# 12_CAN_ADC_DAC.net
KiCad netlist of a schematic drawn in Altium Designer
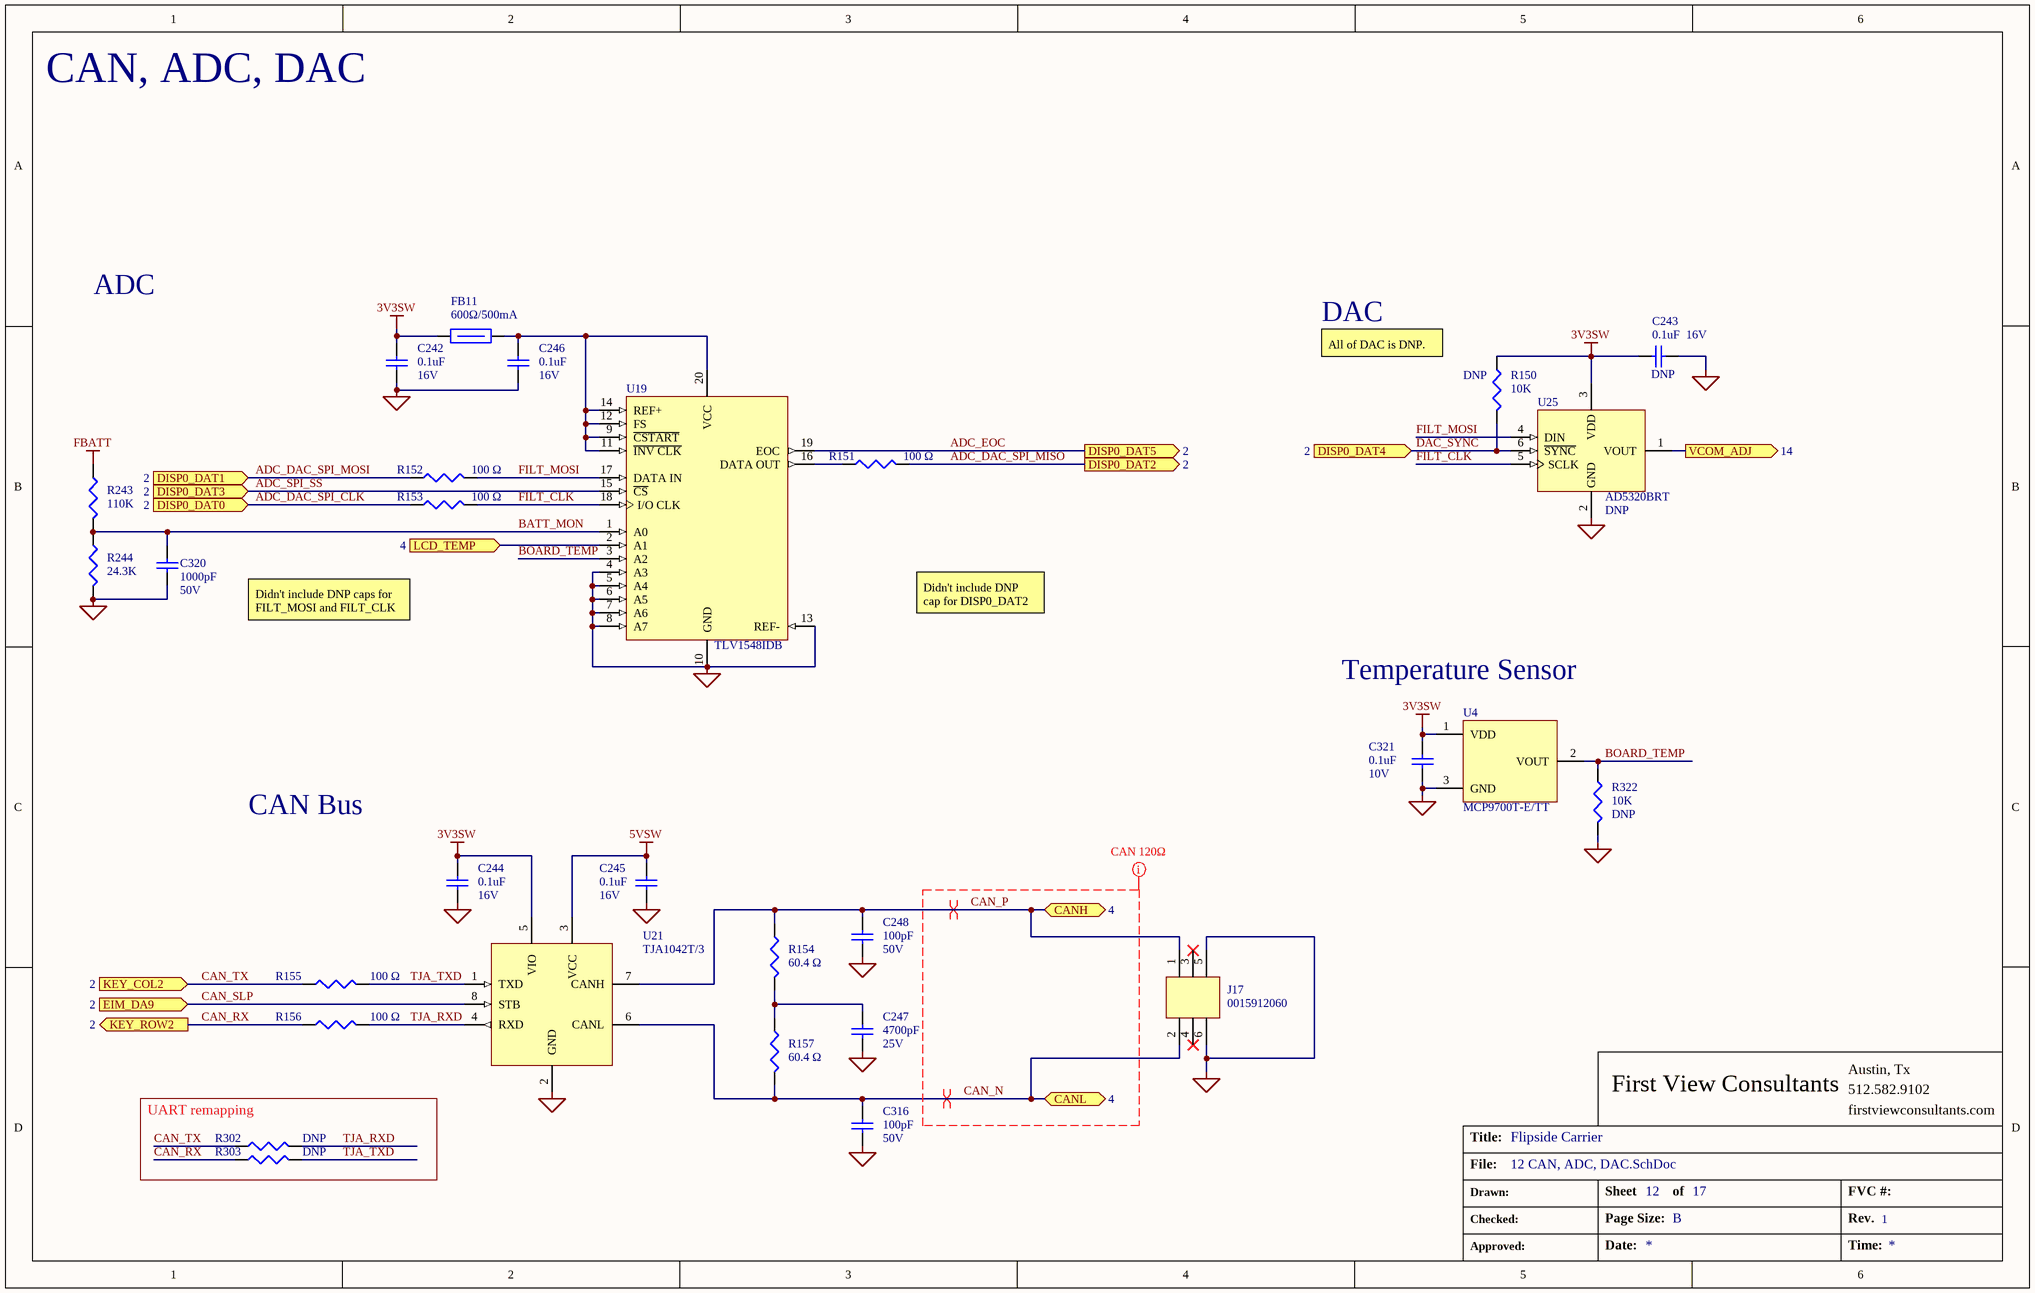
[diagram p0: 12 CAN, ADC, DAC.SchDoc]

(export (version "E")
  (design (tool "Eeschema 10.0.6"))
  (components
    (comp (ref "C242")
      (value "0.1uF")
      (footprint "CAP_0402")
      (description "Cap, Cer, 0.1uF, 16V, 10%, X7R, 0402")
      (fields
        (field (name "TOLERANCE") "±10%")
        (field (name "MANUFACTURER") "Murata Electronics North America")
        (field (name "VOLTAGE") "16V")
      )
      (libsource (lib "Firstview") (part "Cap 0.1uF 16V 0402"))
    )
    (comp (ref "C243")
      (value "0.1uF")
      (footprint "CAP_0402")
      (description "Cap, Cer, 0.1uF, 16V, 10%, X7R, 0402")
      (fields
        (field (name "TOLERANCE") "±10%")
        (field (name "DNP") "DNP")
        (field (name "MANUFACTURER") "Murata Electronics North America")
        (field (name "VOLTAGE") "16V")
      )
      (libsource (lib "Firstview") (part "Cap 0.1uF 16V 0402"))
    )
    (comp (ref "C244")
      (value "0.1uF")
      (footprint "CAP_0402")
      (description "Cap, Cer, 0.1uF, 16V, 10%, X7R, 0402")
      (fields
        (field (name "TOLERANCE") "±10%")
        (field (name "MANUFACTURER") "Murata Electronics North America")
        (field (name "VOLTAGE") "16V")
      )
      (libsource (lib "Firstview") (part "Cap 0.1uF 16V 0402"))
    )
    (comp (ref "C245")
      (value "0.1uF")
      (footprint "CAP_0402")
      (description "Cap, Cer, 0.1uF, 16V, 10%, X7R, 0402")
      (fields
        (field (name "TOLERANCE") "±10%")
        (field (name "MANUFACTURER") "Murata Electronics North America")
        (field (name "VOLTAGE") "16V")
      )
      (libsource (lib "Firstview") (part "Cap 0.1uF 16V 0402"))
    )
    (comp (ref "C246")
      (value "0.1uF")
      (footprint "CAP_0402")
      (description "Cap, Cer, 0.1uF, 16V, 10%, X7R, 0402")
      (fields
        (field (name "TOLERANCE") "±10%")
        (field (name "MANUFACTURER") "Murata Electronics North America")
        (field (name "VOLTAGE") "16V")
      )
      (libsource (lib "Firstview") (part "Cap 0.1uF 16V 0402"))
    )
    (comp (ref "C247")
      (value "4700pF")
      (footprint "CAP_0603")
      (description "Cap, Cer, 4700pF, 25V, 5%, C0G, 0603")
      (fields
        (field (name "TOLERANCE") "5%")
        (field (name "MANUFACTURER") "TDK Corporation")
        (field (name "VOLTAGE") "25V")
      )
      (libsource (lib "Firstview") (part "Cap 4700pF 25V 0603"))
    )
    (comp (ref "C248")
      (value "100pF")
      (footprint "CAP_0402")
      (description "Cap, Cer, 100pF, 50V, 5%, C0G/NP0, 0402")
      (fields
        (field (name "TOLERANCE") "5%")
        (field (name "MANUFACTURER") "Yageo")
        (field (name "VOLTAGE") "50V")
      )
      (libsource (lib "Firstview") (part "Cap 100pF 50V 0402"))
    )
    (comp (ref "C316")
      (value "100pF")
      (footprint "CAP_0402")
      (description "Cap, Cer, 100pF, 50V, 5%, C0G/NP0, 0402")
      (fields
        (field (name "TOLERANCE") "5%")
        (field (name "MANUFACTURER") "Yageo")
        (field (name "VOLTAGE") "50V")
      )
      (libsource (lib "Firstview") (part "Cap 100pF 50V 0402"))
    )
    (comp (ref "C320")
      (value "1000pF")
      (footprint "CAP_0402")
      (description "Cap, Cer, 1000pF, 50V, 20%, X7R, 0402")
      (fields
        (field (name "TOLERANCE") "20%")
        (field (name "MANUFACTURER") "Murata Electronics North America")
        (field (name "VOLTAGE") "50V")
      )
      (libsource (lib "Firstview") (part "Cap 1000pF 50V 0402"))
    )
    (comp (ref "C321")
      (value "0.1uF")
      (footprint "CAP_0402")
      (description "Cap, Cer, 0.1uF, 10V, 10%, X5R, 0402")
      (fields
        (field (name "TOLERANCE") "±10%")
        (field (name "MANUFACTURER") "Murata Electronics North America")
        (field (name "VOLTAGE") "10V")
      )
      (libsource (lib "Firstview") (part "Cap 0.1uF 10V 0402"))
    )
    (comp (ref "FB11")
      (value "600Ω/500mA")
      (footprint "IND_0603")
      (description "Ind, Ferrite Bead, 600R, 350mOhm, 0.5A, 0603")
      (fields
        (field (name "MANUFACTURER") "Murata Electronics North America")
        (field (name "Comment") "BLM18EG601SN1D")
      )
      (libsource (lib "Firstview") (part "BLM18EG601SN1D"))
    )
    (comp (ref "J17")
      (value "0015912060")
      (footprint "CON_0015912060")
      (description "Conn, Header, 6 pos, 0.1\" pitch, SMD")
      (fields (field (name "MANUFACTURER") "Molex Inc"))
      (libsource (lib "Firstview") (part "0015912060"))
    )
    (comp (ref "R150")
      (value "10K")
      (footprint "RES_0402")
      (description "Res, 10K, 1/16W, 1%, 0402")
      (fields
        (field (name "DNP") "DNP")
        (field (name "MANUFACTURER") "Yageo")
        (field (name "Comment") "Res 10K 0.063W")
      )
      (libsource (lib "Firstview") (part "Res 10K 0.063W"))
    )
    (comp (ref "R151")
      (value "100 Ω")
      (footprint "RES_0402")
      (description "Res, 100R, 0.063W, 1%, 0402")
      (fields
        (field (name "MANUFACTURER") "Murata Electronics North America")
        (field (name "Comment") "Res 100R 0.063W")
      )
      (libsource (lib "Firstview") (part "Res 100R 0.063W"))
    )
    (comp (ref "R152")
      (value "100 Ω")
      (footprint "RES_0402")
      (description "Res, 100R, 0.063W, 1%, 0402")
      (fields
        (field (name "MANUFACTURER") "Murata Electronics North America")
        (field (name "Comment") "Res 100R 0.063W")
      )
      (libsource (lib "Firstview") (part "Res 100R 0.063W"))
    )
    (comp (ref "R153")
      (value "100 Ω")
      (footprint "RES_0402")
      (description "Res, 100R, 0.063W, 1%, 0402")
      (fields
        (field (name "MANUFACTURER") "Murata Electronics North America")
        (field (name "Comment") "Res 100R 0.063W")
      )
      (libsource (lib "Firstview") (part "Res 100R 0.063W"))
    )
    (comp (ref "R154")
      (value "60.4 Ω")
      (footprint "RES_0402")
      (description "Res, 60.4, 1/16W, 1%, 0402")
      (fields
        (field (name "MANUFACTURER") "Stackpole Electronics Inc")
        (field (name "Comment") "Res 60.4R 0.063W")
      )
      (libsource (lib "Firstview") (part "Res 60.4R 0.063W"))
    )
    (comp (ref "R155")
      (value "100 Ω")
      (footprint "RES_0402")
      (description "Res, 100R, 0.063W, 1%, 0402")
      (fields
        (field (name "MANUFACTURER") "Murata Electronics North America")
        (field (name "Comment") "Res 100R 0.063W")
      )
      (libsource (lib "Firstview") (part "Res 100R 0.063W"))
    )
    (comp (ref "R156")
      (value "100 Ω")
      (footprint "RES_0402")
      (description "Res, 100R, 0.063W, 1%, 0402")
      (fields
        (field (name "MANUFACTURER") "Murata Electronics North America")
        (field (name "Comment") "Res 100R 0.063W")
      )
      (libsource (lib "Firstview") (part "Res 100R 0.063W"))
    )
    (comp (ref "R157")
      (value "60.4 Ω")
      (footprint "RES_0402")
      (description "Res, 60.4, 1/16W, 1%, 0402")
      (fields
        (field (name "MANUFACTURER") "Stackpole Electronics Inc")
        (field (name "Comment") "Res 60.4R 0.063W")
      )
      (libsource (lib "Firstview") (part "Res 60.4R 0.063W"))
    )
    (comp (ref "R243")
      (value "110K")
      (footprint "RES_0402")
      (description "Res, 110K, 0.063W, 5%, 0402")
      (fields (field (name "TOLERANCE") "5%") (field (name "MANUFACTURER") "Rohm Semiconductor"))
      (libsource (lib "Firstview") (part "Res 110K 0.063W"))
    )
    (comp (ref "R244")
      (value "24.3K")
      (footprint "RES_0402")
      (description "Res, 24.3K, 0.063W, 5%, 0402")
      (fields (field (name "TOLERANCE") "1%") (field (name "MANUFACTURER") "Stackpole Electronics Inc"))
      (libsource (lib "Firstview") (part "Res 24.3K 0.063W"))
    )
    (comp (ref "R302")
      (value "Res 100R 0.063W")
      (footprint "RES_0402")
      (description "Res, 100R, 0.063W, 1%, 0402")
      (fields (field (name "DNP") "DNP") (field (name "MANUFACTURER") "Murata Electronics North America"))
      (libsource (lib "Firstview") (part "Res 100R 0.063W"))
    )
    (comp (ref "R303")
      (value "Res 100R 0.063W")
      (footprint "RES_0402")
      (description "Res, 100R, 0.063W, 1%, 0402")
      (fields (field (name "DNP") "DNP") (field (name "MANUFACTURER") "Murata Electronics North America"))
      (libsource (lib "Firstview") (part "Res 100R 0.063W"))
    )
    (comp (ref "R322")
      (value "10K")
      (footprint "RES_0402")
      (description "Res, 10K, 1/16W, 1%, 0402")
      (fields
        (field (name "DNP") "DNP")
        (field (name "MANUFACTURER") "Yageo")
        (field (name "Comment") "Res 10K 0.063W")
      )
      (libsource (lib "Firstview") (part "Res 10K 0.063W"))
    )
    (comp (ref "U4")
      (value "MCP9700T-E/TT")
      (footprint "SOT-23-3_MCP9700T-E/TT")
      (description "IC, Temp Sensor, 0-70°C, 2.3-5.5V, VSOT-23-3")
      (fields (field (name "MANUFACTURER") "Microchip Technology"))
      (libsource (lib "Firstview") (part "MCP9700T-E/TT"))
    )
    (comp (ref "U19")
      (value "TLV1548IDB")
      (footprint "SSOP-20_TLV1548IDB")
      (description "IC, ADC, 8-ch, 10-Bit, SER, 85Ksps, SSOP-20")
      (fields (field (name "MANUFACTURER") "Texas Instruments"))
      (libsource (lib "Firstview") (part "TLV1548IDB"))
    )
    (comp (ref "U21")
      (value "TJA1042T/3")
      (footprint "SOIC-8_TJA1042T/3")
      (description "IC, CAN, 3-5V, SOIC-8")
      (fields (field (name "MANUFACTURER") "NXP Semiconductor"))
      (libsource (lib "Firstview") (part "TJA1042T/3"))
    )
    (comp (ref "U25")
      (value "AD5320BRT")
      (footprint "SOT-23-6_AD5320BRT")
      (description "IC, DAC, 12-Bit, 2.7-5.5V, 140uA, SOT-23")
      (fields (field (name "DNP") "DNP") (field (name "MANUFACTURER") "Analog Devices"))
      (libsource (lib "Firstview") (part "AD5320BRT"))
    )
  )
  (nets
    (net (code "1") (name "/ADC_DAC_SPI_CLK") (class "Default")
      (node (ref "R153") (pin "1") (pinfunction "1_1") (pintype "passive"))
    )
    (net (code "2") (name "/ADC_DAC_SPI_MISO") (class "Default")
      (node (ref "R151") (pin "2") (pinfunction "2_2") (pintype "passive"))
    )
    (net (code "3") (name "/ADC_DAC_SPI_MOSI") (class "Default")
      (node (ref "R152") (pin "1") (pinfunction "1_1") (pintype "passive"))
    )
    (net (code "4") (name "/ADC_EOC") (class "Default")
      (node (ref "U19") (pin "19") (pinfunction "EOC_19") (pintype "output"))
    )
    (net (code "5") (name "/ADC_SPI_SS") (class "Default")
      (node (ref "U19") (pin "15") (pinfunction "~{CS}_15") (pintype "input"))
    )
    (net (code "6") (name "/BATT_MON") (class "Default")
      (node (ref "C320") (pin "1") (pinfunction "1_1") (pintype "passive"))
      (node (ref "R243") (pin "2") (pinfunction "2_2") (pintype "passive"))
      (node (ref "R244") (pin "1") (pinfunction "1_1") (pintype "passive"))
      (node (ref "U19") (pin "1") (pinfunction "A0_1") (pintype "input"))
    )
    (net (code "7") (name "/BOARD_TEMP") (class "Default")
      (node (ref "R322") (pin "1") (pinfunction "1_1") (pintype "passive"))
      (node (ref "U19") (pin "3") (pinfunction "A2_3") (pintype "input"))
      (node (ref "U4") (pin "2") (pinfunction "VOUT_2") (pintype "power_in"))
    )
    (net (code "8") (name "/CAN_N") (class "Default")
      (node (ref "C316") (pin "1") (pinfunction "1_1") (pintype "passive"))
      (node (ref "J17") (pin "2") (pinfunction "2_2") (pintype "passive"))
      (node (ref "R157") (pin "2") (pinfunction "2_2") (pintype "passive"))
      (node (ref "U21") (pin "6") (pinfunction "CANL_6") (pintype "passive"))
    )
    (net (code "9") (name "/CAN_P") (class "Default")
      (node (ref "C248") (pin "1") (pinfunction "1_1") (pintype "passive"))
      (node (ref "J17") (pin "1") (pinfunction "1_1") (pintype "passive"))
      (node (ref "R154") (pin "1") (pinfunction "1_1") (pintype "passive"))
      (node (ref "U21") (pin "7") (pinfunction "CANH_7") (pintype "passive"))
    )
    (net (code "10") (name "/CAN_RX") (class "Default")
      (node (ref "R156") (pin "1") (pinfunction "1_1") (pintype "passive"))
      (node (ref "R303") (pin "1") (pinfunction "1_1") (pintype "passive"))
    )
    (net (code "11") (name "/CAN_SLP") (class "Default")
      (node (ref "U21") (pin "8") (pinfunction "STB_8") (pintype "input"))
    )
    (net (code "12") (name "/CAN_TX") (class "Default")
      (node (ref "R155") (pin "1") (pinfunction "1_1") (pintype "passive"))
      (node (ref "R302") (pin "1") (pinfunction "1_1") (pintype "passive"))
    )
    (net (code "13") (name "/DAC_SYNC") (class "Default")
      (node (ref "R150") (pin "2") (pinfunction "2_2") (pintype "passive"))
      (node (ref "U25") (pin "6") (pinfunction "~{SYNC}_6") (pintype "input"))
    )
    (net (code "14") (name "/FILT_CLK") (class "Default")
      (node (ref "R153") (pin "2") (pinfunction "2_2") (pintype "passive"))
      (node (ref "U19") (pin "18") (pinfunction "I/O_CLK_18") (pintype "input"))
      (node (ref "U25") (pin "5") (pinfunction "SCLK_5") (pintype "input"))
    )
    (net (code "15") (name "/FILT_MOSI") (class "Default")
      (node (ref "R152") (pin "2") (pinfunction "2_2") (pintype "passive"))
      (node (ref "U19") (pin "17") (pinfunction "DATA_IN_17") (pintype "input"))
      (node (ref "U25") (pin "4") (pinfunction "DIN_4") (pintype "input"))
    )
    (net (code "16") (name "/LCD_TEMP") (class "Default")
      (node (ref "U19") (pin "2") (pinfunction "A1_2") (pintype "input"))
    )
    (net (code "17") (name "/TJA_RXD") (class "Default")
      (node (ref "R156") (pin "2") (pinfunction "2_2") (pintype "passive"))
      (node (ref "R302") (pin "2") (pinfunction "2_2") (pintype "passive"))
      (node (ref "U21") (pin "4") (pinfunction "RXD_4") (pintype "output"))
    )
    (net (code "18") (name "/TJA_TXD") (class "Default")
      (node (ref "R155") (pin "2") (pinfunction "2_2") (pintype "passive"))
      (node (ref "R303") (pin "2") (pinfunction "2_2") (pintype "passive"))
      (node (ref "U21") (pin "1") (pinfunction "TXD_1") (pintype "input"))
    )
    (net (code "19") (name "/VCOM_ADJ") (class "Default")
      (node (ref "U25") (pin "1") (pinfunction "VOUT_1") (pintype "tri_state"))
    )
    (net (code "20") (name "3V3SW") (class "Default")
      (node (ref "C242") (pin "2") (pinfunction "2_2") (pintype "passive"))
      (node (ref "C243") (pin "1") (pinfunction "1_1") (pintype "passive"))
      (node (ref "C244") (pin "1") (pinfunction "1_1") (pintype "passive"))
      (node (ref "C321") (pin "1") (pinfunction "1_1") (pintype "passive"))
      (node (ref "FB11") (pin "1") (pinfunction "1_1") (pintype "passive"))
      (node (ref "R150") (pin "1") (pinfunction "1_1") (pintype "passive"))
      (node (ref "U21") (pin "5") (pinfunction "VIO_5") (pintype "power_in"))
      (node (ref "U25") (pin "3") (pinfunction "VDD_3") (pintype "power_in"))
      (node (ref "U4") (pin "1") (pinfunction "VDD_1") (pintype "power_in"))
    )
    (net (code "21") (name "5VSW") (class "Default")
      (node (ref "C245") (pin "1") (pinfunction "1_1") (pintype "passive"))
      (node (ref "U21") (pin "3") (pinfunction "VCC_3") (pintype "power_in"))
    )
    (net (code "22") (name "FBATT") (class "Default")
      (node (ref "R243") (pin "1") (pinfunction "1_1") (pintype "passive"))
    )
    (net (code "23") (name "GND") (class "Default")
      (node (ref "C242") (pin "1") (pinfunction "1_1") (pintype "passive"))
      (node (ref "C243") (pin "2") (pinfunction "2_2") (pintype "passive"))
      (node (ref "C244") (pin "2") (pinfunction "2_2") (pintype "passive"))
      (node (ref "C245") (pin "2") (pinfunction "2_2") (pintype "passive"))
      (node (ref "C246") (pin "1") (pinfunction "1_1") (pintype "passive"))
      (node (ref "C247") (pin "2") (pinfunction "2_2") (pintype "passive"))
      (node (ref "C248") (pin "2") (pinfunction "2_2") (pintype "passive"))
      (node (ref "C316") (pin "2") (pinfunction "2_2") (pintype "passive"))
      (node (ref "C320") (pin "2") (pinfunction "2_2") (pintype "passive"))
      (node (ref "C321") (pin "2") (pinfunction "2_2") (pintype "passive"))
      (node (ref "J17") (pin "5") (pinfunction "5_5") (pintype "passive"))
      (node (ref "J17") (pin "6") (pinfunction "6_6") (pintype "passive"))
      (node (ref "R244") (pin "2") (pinfunction "2_2") (pintype "passive"))
      (node (ref "R322") (pin "2") (pinfunction "2_2") (pintype "passive"))
      (node (ref "U19") (pin "10") (pinfunction "GND_10") (pintype "power_in"))
      (node (ref "U19") (pin "13") (pinfunction "REF-_13") (pintype "input"))
      (node (ref "U19") (pin "4") (pinfunction "A3_4") (pintype "input"))
      (node (ref "U19") (pin "5") (pinfunction "A4_5") (pintype "input"))
      (node (ref "U19") (pin "6") (pinfunction "A5_6") (pintype "input"))
      (node (ref "U19") (pin "7") (pinfunction "A6_7") (pintype "input"))
      (node (ref "U19") (pin "8") (pinfunction "A7_8") (pintype "input"))
      (node (ref "U21") (pin "2") (pinfunction "GND_2") (pintype "power_in"))
      (node (ref "U25") (pin "2") (pinfunction "GND_2") (pintype "power_in"))
      (node (ref "U4") (pin "3") (pinfunction "GND_3") (pintype "power_in"))
    )
    (net (code "24") (name "Net-(C247-Pad1)") (class "Default")
      (node (ref "C247") (pin "1") (pinfunction "1_1") (pintype "passive"))
      (node (ref "R154") (pin "2") (pinfunction "2_2") (pintype "passive"))
      (node (ref "R157") (pin "1") (pinfunction "1_1") (pintype "passive"))
    )
    (net (code "25") (name "Net-(U19-DATA_OUT)") (class "Default")
      (node (ref "R151") (pin "1") (pinfunction "1_1") (pintype "passive"))
      (node (ref "U19") (pin "16") (pinfunction "DATA_OUT_16") (pintype "output"))
    )
    (net (code "26") (name "Net-(U19-FS)") (class "Default")
      (node (ref "C246") (pin "2") (pinfunction "2_2") (pintype "passive"))
      (node (ref "FB11") (pin "2") (pinfunction "2_2") (pintype "passive"))
      (node (ref "U19") (pin "11") (pinfunction "~{INV_CLK}_11") (pintype "input"))
      (node (ref "U19") (pin "12") (pinfunction "FS_12") (pintype "input"))
      (node (ref "U19") (pin "14") (pinfunction "REF+_14") (pintype "input"))
      (node (ref "U19") (pin "20") (pinfunction "VCC_20") (pintype "power_in"))
      (node (ref "U19") (pin "9") (pinfunction "~{CSTART}_9") (pintype "input"))
    )
    (net (code "27") (name "unconnected-(J17-Pad3)") (class "Default")
      (node (ref "J17") (pin "3") (pinfunction "3_3") (pintype "passive+no_connect"))
    )
    (net (code "28") (name "unconnected-(J17-Pad4)") (class "Default")
      (node (ref "J17") (pin "4") (pinfunction "4_4") (pintype "passive+no_connect"))
    )
  )
)
